# propulsion_shield.net
KiCad netlist of a schematic drawn in EAGLE
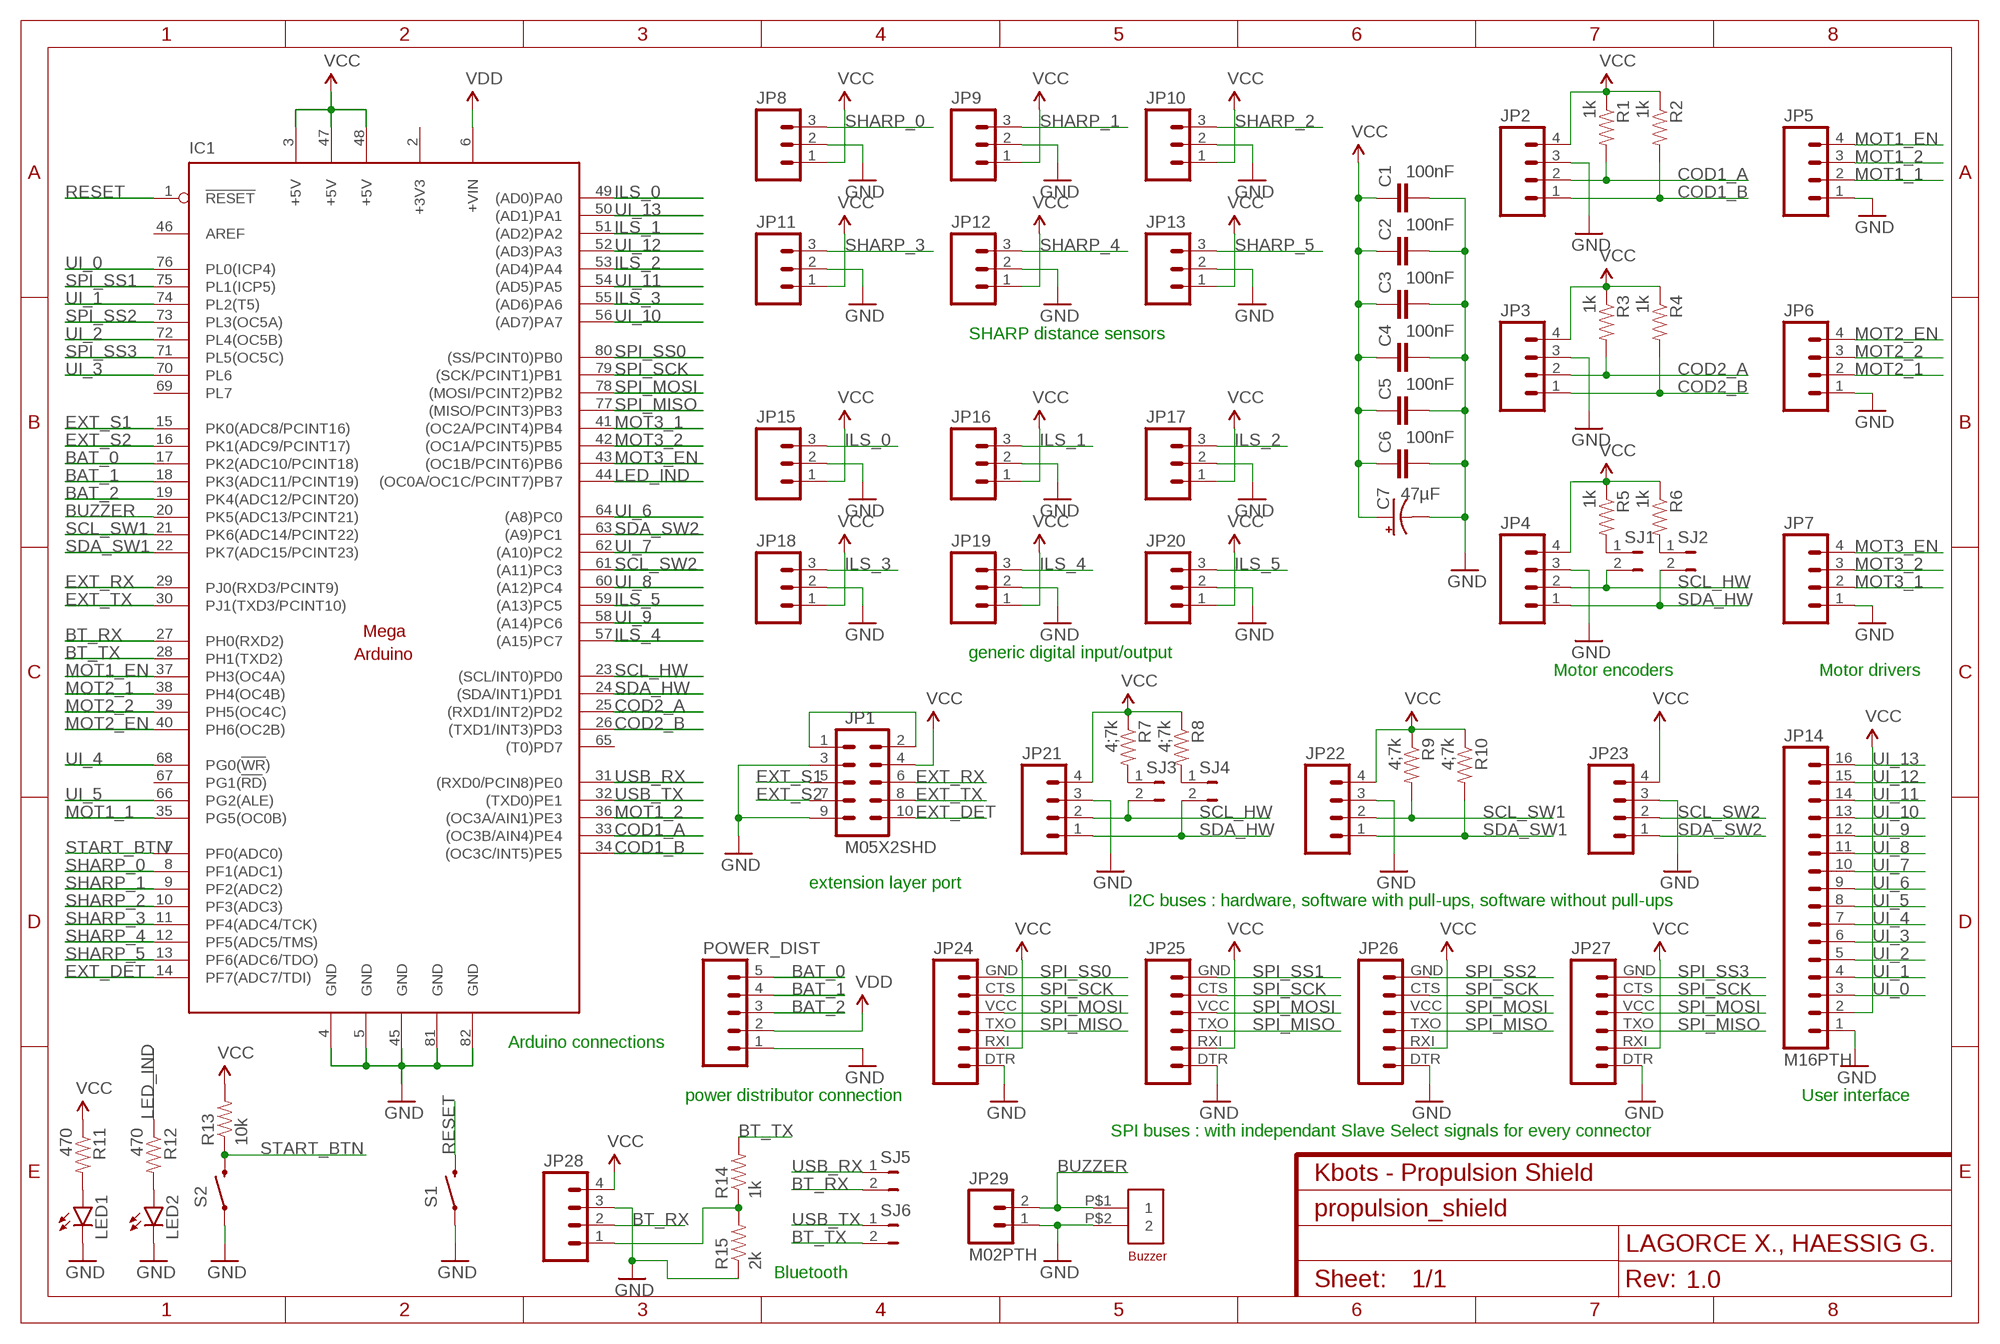
[diagram p0: schematic, sheet 1]

(export (version "E")
  (design (tool "Eeschema 10.0.6"))
  (components
    (comp (ref "C1")
      (value "100nF")
      (footprint "eagle-import:1206")
      (libsource (lib "eagle-import") (part "CAP1206"))
    )
    (comp (ref "C2")
      (value "100nF")
      (footprint "eagle-import:1206")
      (libsource (lib "eagle-import") (part "CAP1206"))
    )
    (comp (ref "C3")
      (value "100nF")
      (footprint "eagle-import:1206")
      (libsource (lib "eagle-import") (part "CAP1206"))
    )
    (comp (ref "C4")
      (value "100nF")
      (footprint "eagle-import:1206")
      (libsource (lib "eagle-import") (part "CAP1206"))
    )
    (comp (ref "C5")
      (value "100nF")
      (footprint "eagle-import:1206")
      (libsource (lib "eagle-import") (part "CAP1206"))
    )
    (comp (ref "C6")
      (value "100nF")
      (footprint "eagle-import:1206")
      (libsource (lib "eagle-import") (part "CAP1206"))
    )
    (comp (ref "C7")
      (value "47µF")
      (footprint "eagle-import:PANASONIC_D")
      (libsource (lib "eagle-import") (part "47UF-50V-20%(ELECT)"))
    )
    (comp (ref "IC1")
      (value "MEGAARDUINO_13")
      (footprint "eagle-import:MEGA_ARDUINO_NO_HOLE")
      (libsource (lib "eagle-import") (part "MEGAARDUINO_13"))
    )
    (comp (ref "JP1")
      (value "M05X2SHD")
      (footprint "eagle-import:2X5-SHROUDED")
      (libsource (lib "eagle-import") (part "M05X2SHD"))
    )
    (comp (ref "JP2")
      (value "M04PTH")
      (footprint "eagle-import:1X04")
      (libsource (lib "eagle-import") (part "M04PTH"))
    )
    (comp (ref "JP3")
      (value "M04PTH")
      (footprint "eagle-import:1X04")
      (libsource (lib "eagle-import") (part "M04PTH"))
    )
    (comp (ref "JP4")
      (value "M04PTH")
      (footprint "eagle-import:1X04")
      (libsource (lib "eagle-import") (part "M04PTH"))
    )
    (comp (ref "JP5")
      (value "M04PTH")
      (footprint "eagle-import:1X04")
      (libsource (lib "eagle-import") (part "M04PTH"))
    )
    (comp (ref "JP6")
      (value "M04PTH")
      (footprint "eagle-import:1X04")
      (libsource (lib "eagle-import") (part "M04PTH"))
    )
    (comp (ref "JP7")
      (value "M04PTH")
      (footprint "eagle-import:1X04")
      (libsource (lib "eagle-import") (part "M04PTH"))
    )
    (comp (ref "JP8")
      (value "M03PTH")
      (footprint "eagle-import:1X03")
      (libsource (lib "eagle-import") (part "M03PTH"))
    )
    (comp (ref "JP9")
      (value "M03PTH")
      (footprint "eagle-import:1X03")
      (libsource (lib "eagle-import") (part "M03PTH"))
    )
    (comp (ref "JP10")
      (value "M03PTH")
      (footprint "eagle-import:1X03")
      (libsource (lib "eagle-import") (part "M03PTH"))
    )
    (comp (ref "JP11")
      (value "M03PTH")
      (footprint "eagle-import:1X03")
      (libsource (lib "eagle-import") (part "M03PTH"))
    )
    (comp (ref "JP12")
      (value "M03PTH")
      (footprint "eagle-import:1X03")
      (libsource (lib "eagle-import") (part "M03PTH"))
    )
    (comp (ref "JP13")
      (value "M03PTH")
      (footprint "eagle-import:1X03")
      (libsource (lib "eagle-import") (part "M03PTH"))
    )
    (comp (ref "JP14")
      (value "M16PTH")
      (footprint "eagle-import:1X16")
      (libsource (lib "eagle-import") (part "M16PTH"))
    )
    (comp (ref "JP15")
      (value "M03PTH")
      (footprint "eagle-import:1X03")
      (libsource (lib "eagle-import") (part "M03PTH"))
    )
    (comp (ref "JP16")
      (value "M03PTH")
      (footprint "eagle-import:1X03")
      (libsource (lib "eagle-import") (part "M03PTH"))
    )
    (comp (ref "JP17")
      (value "M03PTH")
      (footprint "eagle-import:1X03")
      (libsource (lib "eagle-import") (part "M03PTH"))
    )
    (comp (ref "JP18")
      (value "M03PTH")
      (footprint "eagle-import:1X03")
      (libsource (lib "eagle-import") (part "M03PTH"))
    )
    (comp (ref "JP19")
      (value "M03PTH")
      (footprint "eagle-import:1X03")
      (libsource (lib "eagle-import") (part "M03PTH"))
    )
    (comp (ref "JP20")
      (value "M03PTH")
      (footprint "eagle-import:1X03")
      (libsource (lib "eagle-import") (part "M03PTH"))
    )
    (comp (ref "JP21")
      (value "M04PTH")
      (footprint "eagle-import:1X04")
      (libsource (lib "eagle-import") (part "M04PTH"))
    )
    (comp (ref "JP22")
      (value "M04PTH")
      (footprint "eagle-import:1X04")
      (libsource (lib "eagle-import") (part "M04PTH"))
    )
    (comp (ref "JP23")
      (value "M04PTH")
      (footprint "eagle-import:1X04")
      (libsource (lib "eagle-import") (part "M04PTH"))
    )
    (comp (ref "JP24")
      (value "M06SIP")
      (footprint "eagle-import:1X06")
      (libsource (lib "eagle-import") (part "M06SIP"))
    )
    (comp (ref "JP25")
      (value "M06SIP")
      (footprint "eagle-import:1X06")
      (libsource (lib "eagle-import") (part "M06SIP"))
    )
    (comp (ref "JP26")
      (value "M06SIP")
      (footprint "eagle-import:1X06")
      (libsource (lib "eagle-import") (part "M06SIP"))
    )
    (comp (ref "JP27")
      (value "M06SIP")
      (footprint "eagle-import:1X06")
      (libsource (lib "eagle-import") (part "M06SIP"))
    )
    (comp (ref "JP28")
      (value "M04PTH")
      (footprint "eagle-import:1X04")
      (libsource (lib "eagle-import") (part "M04PTH"))
    )
    (comp (ref "JP29")
      (value "M02PTH")
      (footprint "eagle-import:1X02")
      (libsource (lib "eagle-import") (part "M02PTH"))
    )
    (comp (ref "LED1")
      (value "LED1206")
      (footprint "eagle-import:LED-1206")
      (libsource (lib "eagle-import") (part "LED1206"))
    )
    (comp (ref "LED2")
      (value "LED1206")
      (footprint "eagle-import:LED-1206")
      (libsource (lib "eagle-import") (part "LED1206"))
    )
    (comp (ref "POWER_DIST")
      (value "M05PTH")
      (footprint "eagle-import:1X05")
      (libsource (lib "eagle-import") (part "M05PTH"))
    )
    (comp (ref "R1")
      (value "1k")
      (footprint "eagle-import:1206")
      (libsource (lib "eagle-import") (part "RESISTOR1206"))
    )
    (comp (ref "R2")
      (value "1k")
      (footprint "eagle-import:1206")
      (libsource (lib "eagle-import") (part "RESISTOR1206"))
    )
    (comp (ref "R3")
      (value "1k")
      (footprint "eagle-import:1206")
      (libsource (lib "eagle-import") (part "RESISTOR1206"))
    )
    (comp (ref "R4")
      (value "1k")
      (footprint "eagle-import:1206")
      (libsource (lib "eagle-import") (part "RESISTOR1206"))
    )
    (comp (ref "R5")
      (value "1k")
      (footprint "eagle-import:1206")
      (libsource (lib "eagle-import") (part "RESISTOR1206"))
    )
    (comp (ref "R6")
      (value "1k")
      (footprint "eagle-import:1206")
      (libsource (lib "eagle-import") (part "RESISTOR1206"))
    )
    (comp (ref "R7")
      (value "4;7k")
      (footprint "eagle-import:1206")
      (libsource (lib "eagle-import") (part "RESISTOR1206"))
    )
    (comp (ref "R8")
      (value "4;7k")
      (footprint "eagle-import:1206")
      (libsource (lib "eagle-import") (part "RESISTOR1206"))
    )
    (comp (ref "R9")
      (value "4;7k")
      (footprint "eagle-import:1206")
      (libsource (lib "eagle-import") (part "RESISTOR1206"))
    )
    (comp (ref "R10")
      (value "4;7k")
      (footprint "eagle-import:1206")
      (libsource (lib "eagle-import") (part "RESISTOR1206"))
    )
    (comp (ref "R11")
      (value "470")
      (footprint "eagle-import:1206")
      (libsource (lib "eagle-import") (part "RESISTOR1206"))
    )
    (comp (ref "R12")
      (value "470")
      (footprint "eagle-import:1206")
      (libsource (lib "eagle-import") (part "RESISTOR1206"))
    )
    (comp (ref "R13")
      (value "10k")
      (footprint "eagle-import:1206")
      (libsource (lib "eagle-import") (part "RESISTOR1206"))
    )
    (comp (ref "R14")
      (value "1k")
      (footprint "eagle-import:1206")
      (libsource (lib "eagle-import") (part "RESISTOR1206"))
    )
    (comp (ref "R15")
      (value "2k")
      (footprint "eagle-import:1206")
      (libsource (lib "eagle-import") (part "RESISTOR1206"))
    )
    (comp (ref "S1")
      (value "SWITCH-MOMENTARY-2PTH")
      (footprint "eagle-import:TACTILE-PTH")
      (libsource (lib "eagle-import") (part "SWITCH-MOMENTARY-2PTH"))
    )
    (comp (ref "S2")
      (value "SWITCH-MOMENTARY-2PTH")
      (footprint "eagle-import:TACTILE-PTH")
      (libsource (lib "eagle-import") (part "SWITCH-MOMENTARY-2PTH"))
    )
    (comp (ref "SJ1")
      (value "JUMPER-PTH-2-NO")
      (footprint "eagle-import:PTH-JUMPER-2-NO_NO_SILK")
      (libsource (lib "eagle-import") (part "JUMPER-PTH-2-NO"))
    )
    (comp (ref "SJ2")
      (value "JUMPER-PTH-2-NO")
      (footprint "eagle-import:PTH-JUMPER-2-NO_NO_SILK")
      (libsource (lib "eagle-import") (part "JUMPER-PTH-2-NO"))
    )
    (comp (ref "SJ3")
      (value "JUMPER-PTH-2-NO")
      (footprint "eagle-import:PTH-JUMPER-2-NO_NO_SILK")
      (libsource (lib "eagle-import") (part "JUMPER-PTH-2-NO"))
    )
    (comp (ref "SJ4")
      (value "JUMPER-PTH-2-NO")
      (footprint "eagle-import:PTH-JUMPER-2-NO_NO_SILK")
      (libsource (lib "eagle-import") (part "JUMPER-PTH-2-NO"))
    )
    (comp (ref "SJ5")
      (value "JUMPER-PTH-2-NO")
      (footprint "eagle-import:PTH-JUMPER-2-NO_NO_SILK")
      (libsource (lib "eagle-import") (part "JUMPER-PTH-2-NO"))
    )
    (comp (ref "SJ6")
      (value "JUMPER-PTH-2-NO")
      (footprint "eagle-import:PTH-JUMPER-2-NO_NO_SILK")
      (libsource (lib "eagle-import") (part "JUMPER-PTH-2-NO"))
    )
    (comp (ref "U$1")
      (value "BUZZER")
      (footprint "eagle-import:BUZZER")
      (libsource (lib "eagle-import") (part "BUZZER"))
    )
  )
  (nets
    (net (code "1") (name "/+3V3") (class "Default")
      (node (ref "IC1") (pin "2") (pinfunction "+3V3_2") (pintype "power_in"))
    )
    (net (code "2") (name "/BAT_0") (class "Default")
      (node (ref "IC1") (pin "17") (pinfunction "PK2(ADC10/PCINT18)_17") (pintype "bidirectional"))
      (node (ref "POWER_DIST") (pin "5") (pinfunction "5_5") (pintype "passive"))
    )
    (net (code "3") (name "/BAT_1") (class "Default")
      (node (ref "IC1") (pin "18") (pinfunction "PK3(ADC11/PCINT19)_18") (pintype "bidirectional"))
      (node (ref "POWER_DIST") (pin "4") (pinfunction "4_4") (pintype "passive"))
    )
    (net (code "4") (name "/BAT_2") (class "Default")
      (node (ref "IC1") (pin "19") (pinfunction "PK4(ADC12/PCINT20)_19") (pintype "bidirectional"))
      (node (ref "POWER_DIST") (pin "3") (pinfunction "3_3") (pintype "passive"))
    )
    (net (code "5") (name "/BT_RX") (class "Default")
      (node (ref "IC1") (pin "27") (pinfunction "PH0(RXD2)_27") (pintype "bidirectional"))
      (node (ref "JP28") (pin "2") (pinfunction "2_2") (pintype "passive"))
      (node (ref "SJ5") (pin "2") (pinfunction "2_2") (pintype "passive"))
    )
    (net (code "6") (name "/BT_TX") (class "Default")
      (node (ref "IC1") (pin "28") (pinfunction "PH1(TXD2)_28") (pintype "bidirectional"))
      (node (ref "R14") (pin "2") (pinfunction "2_2") (pintype "passive"))
      (node (ref "SJ6") (pin "2") (pinfunction "2_2") (pintype "passive"))
    )
    (net (code "7") (name "/BUZZER") (class "Default")
      (node (ref "IC1") (pin "20") (pinfunction "PK5(ADC13/PCINT21)_20") (pintype "bidirectional"))
      (node (ref "JP29") (pin "2") (pinfunction "2_2") (pintype "passive"))
      (node (ref "U$1") (pin "P$1") (pinfunction "1_P$1") (pintype "bidirectional"))
    )
    (net (code "8") (name "/COD1_A") (class "Default")
      (node (ref "IC1") (pin "33") (pinfunction "(OC3B/AIN4)PE4_33") (pintype "bidirectional"))
      (node (ref "JP2") (pin "2") (pinfunction "2_2") (pintype "passive"))
      (node (ref "R1") (pin "2") (pinfunction "2_2") (pintype "passive"))
    )
    (net (code "9") (name "/COD1_B") (class "Default")
      (node (ref "IC1") (pin "34") (pinfunction "(OC3C/INT5)PE5_34") (pintype "bidirectional"))
      (node (ref "JP2") (pin "1") (pinfunction "1_1") (pintype "passive"))
      (node (ref "R2") (pin "2") (pinfunction "2_2") (pintype "passive"))
    )
    (net (code "10") (name "/COD2_A") (class "Default")
      (node (ref "IC1") (pin "25") (pinfunction "(RXD1/INT2)PD2_25") (pintype "bidirectional"))
      (node (ref "JP3") (pin "2") (pinfunction "2_2") (pintype "passive"))
      (node (ref "R3") (pin "2") (pinfunction "2_2") (pintype "passive"))
    )
    (net (code "11") (name "/COD2_B") (class "Default")
      (node (ref "IC1") (pin "26") (pinfunction "(TXD1/INT3)PD3_26") (pintype "bidirectional"))
      (node (ref "JP3") (pin "1") (pinfunction "1_1") (pintype "passive"))
      (node (ref "R4") (pin "2") (pinfunction "2_2") (pintype "passive"))
    )
    (net (code "12") (name "/EXT_DET") (class "Default")
      (node (ref "IC1") (pin "14") (pinfunction "PF7(ADC7/TDI)_14") (pintype "bidirectional"))
      (node (ref "JP1") (pin "10") (pinfunction "10_10") (pintype "passive"))
    )
    (net (code "13") (name "/EXT_RX") (class "Default")
      (node (ref "IC1") (pin "29") (pinfunction "PJ0(RXD3/PCINT9)_29") (pintype "bidirectional"))
      (node (ref "JP1") (pin "6") (pinfunction "6_6") (pintype "passive"))
    )
    (net (code "14") (name "/EXT_S1") (class "Default")
      (node (ref "IC1") (pin "15") (pinfunction "PK0(ADC8/PCINT16)_15") (pintype "bidirectional"))
      (node (ref "JP1") (pin "5") (pinfunction "5_5") (pintype "passive"))
    )
    (net (code "15") (name "/EXT_S2") (class "Default")
      (node (ref "IC1") (pin "16") (pinfunction "PK1(ADC9/PCINT17)_16") (pintype "bidirectional"))
      (node (ref "JP1") (pin "7") (pinfunction "7_7") (pintype "passive"))
    )
    (net (code "16") (name "/EXT_TX") (class "Default")
      (node (ref "IC1") (pin "30") (pinfunction "PJ1(TXD3/PCINT10)_30") (pintype "bidirectional"))
      (node (ref "JP1") (pin "8") (pinfunction "8_8") (pintype "passive"))
    )
    (net (code "17") (name "/ILS_0") (class "Default")
      (node (ref "IC1") (pin "49") (pinfunction "(AD0)PA0_49") (pintype "bidirectional"))
      (node (ref "JP15") (pin "3") (pinfunction "3_3") (pintype "passive"))
    )
    (net (code "18") (name "/ILS_1") (class "Default")
      (node (ref "IC1") (pin "51") (pinfunction "(AD2)PA2_51") (pintype "bidirectional"))
      (node (ref "JP16") (pin "3") (pinfunction "3_3") (pintype "passive"))
    )
    (net (code "19") (name "/ILS_2") (class "Default")
      (node (ref "IC1") (pin "53") (pinfunction "(AD4)PA4_53") (pintype "bidirectional"))
      (node (ref "JP17") (pin "3") (pinfunction "3_3") (pintype "passive"))
    )
    (net (code "20") (name "/ILS_3") (class "Default")
      (node (ref "IC1") (pin "55") (pinfunction "(AD6)PA6_55") (pintype "bidirectional"))
      (node (ref "JP18") (pin "3") (pinfunction "3_3") (pintype "passive"))
    )
    (net (code "21") (name "/ILS_4") (class "Default")
      (node (ref "IC1") (pin "57") (pinfunction "(A15)PC7_57") (pintype "bidirectional"))
      (node (ref "JP19") (pin "3") (pinfunction "3_3") (pintype "passive"))
    )
    (net (code "22") (name "/ILS_5") (class "Default")
      (node (ref "IC1") (pin "59") (pinfunction "(A13)PC5_59") (pintype "bidirectional"))
      (node (ref "JP20") (pin "3") (pinfunction "3_3") (pintype "passive"))
    )
    (net (code "23") (name "/LED_IND") (class "Default")
      (node (ref "IC1") (pin "44") (pinfunction "(OC0A/OC1C/PCINT7)PB7_44") (pintype "bidirectional"))
      (node (ref "R12") (pin "1") (pinfunction "1_1") (pintype "passive"))
    )
    (net (code "24") (name "/MOT1_1") (class "Default")
      (node (ref "IC1") (pin "35") (pinfunction "PG5(OC0B)_35") (pintype "bidirectional"))
      (node (ref "JP5") (pin "2") (pinfunction "2_2") (pintype "passive"))
    )
    (net (code "25") (name "/MOT1_2") (class "Default")
      (node (ref "IC1") (pin "36") (pinfunction "(OC3A/AIN1)PE3_36") (pintype "bidirectional"))
      (node (ref "JP5") (pin "3") (pinfunction "3_3") (pintype "passive"))
    )
    (net (code "26") (name "/MOT1_EN") (class "Default")
      (node (ref "IC1") (pin "37") (pinfunction "PH3(OC4A)_37") (pintype "bidirectional"))
      (node (ref "JP5") (pin "4") (pinfunction "4_4") (pintype "passive"))
    )
    (net (code "27") (name "/MOT2_1") (class "Default")
      (node (ref "IC1") (pin "38") (pinfunction "PH4(OC4B)_38") (pintype "bidirectional"))
      (node (ref "JP6") (pin "2") (pinfunction "2_2") (pintype "passive"))
    )
    (net (code "28") (name "/MOT2_2") (class "Default")
      (node (ref "IC1") (pin "39") (pinfunction "PH5(OC4C)_39") (pintype "bidirectional"))
      (node (ref "JP6") (pin "3") (pinfunction "3_3") (pintype "passive"))
    )
    (net (code "29") (name "/MOT2_EN") (class "Default")
      (node (ref "IC1") (pin "40") (pinfunction "PH6(OC2B)_40") (pintype "bidirectional"))
      (node (ref "JP6") (pin "4") (pinfunction "4_4") (pintype "passive"))
    )
    (net (code "30") (name "/MOT3_1") (class "Default")
      (node (ref "IC1") (pin "41") (pinfunction "(OC2A/PCINT4)PB4_41") (pintype "bidirectional"))
      (node (ref "JP7") (pin "2") (pinfunction "2_2") (pintype "passive"))
    )
    (net (code "31") (name "/MOT3_2") (class "Default")
      (node (ref "IC1") (pin "42") (pinfunction "(OC1A/PCINT5)PB5_42") (pintype "bidirectional"))
      (node (ref "JP7") (pin "3") (pinfunction "3_3") (pintype "passive"))
    )
    (net (code "32") (name "/MOT3_EN") (class "Default")
      (node (ref "IC1") (pin "43") (pinfunction "(OC1B/PCINT6)PB6_43") (pintype "bidirectional"))
      (node (ref "JP7") (pin "4") (pinfunction "4_4") (pintype "passive"))
    )
    (net (code "33") (name "/RESET") (class "Default")
      (node (ref "IC1") (pin "1") (pinfunction "~{RESET}_1") (pintype "bidirectional"))
      (node (ref "S1") (pin "3") (pinfunction "2_3") (pintype "passive"))
    )
    (net (code "34") (name "/SCL_HW") (class "Default")
      (node (ref "IC1") (pin "23") (pinfunction "(SCL/INT0)PD0_23") (pintype "bidirectional"))
      (node (ref "JP21") (pin "2") (pinfunction "2_2") (pintype "passive"))
      (node (ref "JP4") (pin "2") (pinfunction "2_2") (pintype "passive"))
      (node (ref "SJ1") (pin "2") (pinfunction "2_2") (pintype "passive"))
      (node (ref "SJ3") (pin "2") (pinfunction "2_2") (pintype "passive"))
    )
    (net (code "35") (name "/SCL_SW1") (class "Default")
      (node (ref "IC1") (pin "21") (pinfunction "PK6(ADC14/PCINT22)_21") (pintype "bidirectional"))
      (node (ref "JP22") (pin "2") (pinfunction "2_2") (pintype "passive"))
      (node (ref "R9") (pin "2") (pinfunction "2_2") (pintype "passive"))
    )
    (net (code "36") (name "/SCL_SW2") (class "Default")
      (node (ref "IC1") (pin "61") (pinfunction "(A11)PC3_61") (pintype "bidirectional"))
      (node (ref "JP23") (pin "2") (pinfunction "2_2") (pintype "passive"))
    )
    (net (code "37") (name "/SDA_HW") (class "Default")
      (node (ref "IC1") (pin "24") (pinfunction "(SDA/INT1)PD1_24") (pintype "bidirectional"))
      (node (ref "JP21") (pin "1") (pinfunction "1_1") (pintype "passive"))
      (node (ref "JP4") (pin "1") (pinfunction "1_1") (pintype "passive"))
      (node (ref "SJ2") (pin "2") (pinfunction "2_2") (pintype "passive"))
      (node (ref "SJ4") (pin "2") (pinfunction "2_2") (pintype "passive"))
    )
    (net (code "38") (name "/SDA_SW1") (class "Default")
      (node (ref "IC1") (pin "22") (pinfunction "PK7(ADC15/PCINT23)_22") (pintype "bidirectional"))
      (node (ref "JP22") (pin "1") (pinfunction "1_1") (pintype "passive"))
      (node (ref "R10") (pin "2") (pinfunction "2_2") (pintype "passive"))
    )
    (net (code "39") (name "/SDA_SW2") (class "Default")
      (node (ref "IC1") (pin "63") (pinfunction "(A9)PC1_63") (pintype "bidirectional"))
      (node (ref "JP23") (pin "1") (pinfunction "1_1") (pintype "passive"))
    )
    (net (code "40") (name "/SHARP_0") (class "Default")
      (node (ref "IC1") (pin "8") (pinfunction "PF1(ADC1)_8") (pintype "bidirectional"))
      (node (ref "JP8") (pin "3") (pinfunction "3_3") (pintype "passive"))
    )
    (net (code "41") (name "/SHARP_1") (class "Default")
      (node (ref "IC1") (pin "9") (pinfunction "PF2(ADC2)_9") (pintype "bidirectional"))
      (node (ref "JP9") (pin "3") (pinfunction "3_3") (pintype "passive"))
    )
    (net (code "42") (name "/SHARP_2") (class "Default")
      (node (ref "IC1") (pin "10") (pinfunction "PF3(ADC3)_10") (pintype "bidirectional"))
      (node (ref "JP10") (pin "3") (pinfunction "3_3") (pintype "passive"))
    )
    (net (code "43") (name "/SHARP_3") (class "Default")
      (node (ref "IC1") (pin "11") (pinfunction "PF4(ADC4/TCK)_11") (pintype "bidirectional"))
      (node (ref "JP11") (pin "3") (pinfunction "3_3") (pintype "passive"))
    )
    (net (code "44") (name "/SHARP_4") (class "Default")
      (node (ref "IC1") (pin "12") (pinfunction "PF5(ADC5/TMS)_12") (pintype "bidirectional"))
      (node (ref "JP12") (pin "3") (pinfunction "3_3") (pintype "passive"))
    )
    (net (code "45") (name "/SHARP_5") (class "Default")
      (node (ref "IC1") (pin "13") (pinfunction "PF6(ADC6/TDO)_13") (pintype "bidirectional"))
      (node (ref "JP13") (pin "3") (pinfunction "3_3") (pintype "passive"))
    )
    (net (code "46") (name "/SPI_MISO") (class "Default")
      (node (ref "IC1") (pin "77") (pinfunction "(MISO/PCINT3)PB3_77") (pintype "bidirectional"))
      (node (ref "JP24") (pin "TXO") (pinfunction "3_TXO") (pintype "passive"))
      (node (ref "JP25") (pin "TXO") (pinfunction "3_TXO") (pintype "passive"))
      (node (ref "JP26") (pin "TXO") (pinfunction "3_TXO") (pintype "passive"))
      (node (ref "JP27") (pin "TXO") (pinfunction "3_TXO") (pintype "passive"))
    )
    (net (code "47") (name "/SPI_MOSI") (class "Default")
      (node (ref "IC1") (pin "78") (pinfunction "(MOSI/PCINT2)PB2_78") (pintype "bidirectional"))
      (node (ref "JP24") (pin "VCC") (pinfunction "4_VCC") (pintype "passive"))
      (node (ref "JP25") (pin "VCC") (pinfunction "4_VCC") (pintype "passive"))
      (node (ref "JP26") (pin "VCC") (pinfunction "4_VCC") (pintype "passive"))
      (node (ref "JP27") (pin "VCC") (pinfunction "4_VCC") (pintype "passive"))
    )
    (net (code "48") (name "/SPI_SCK") (class "Default")
      (node (ref "IC1") (pin "79") (pinfunction "(SCK/PCINT1)PB1_79") (pintype "bidirectional"))
      (node (ref "JP24") (pin "CTS") (pinfunction "5_CTS") (pintype "passive"))
      (node (ref "JP25") (pin "CTS") (pinfunction "5_CTS") (pintype "passive"))
      (node (ref "JP26") (pin "CTS") (pinfunction "5_CTS") (pintype "passive"))
      (node (ref "JP27") (pin "CTS") (pinfunction "5_CTS") (pintype "passive"))
    )
    (net (code "49") (name "/SPI_SS0") (class "Default")
      (node (ref "IC1") (pin "80") (pinfunction "(SS/PCINT0)PB0_80") (pintype "bidirectional"))
      (node (ref "JP24") (pin "GND") (pinfunction "6_GND") (pintype "passive"))
    )
    (net (code "50") (name "/SPI_SS1") (class "Default")
      (node (ref "IC1") (pin "75") (pinfunction "PL1(ICP5)_75") (pintype "bidirectional"))
      (node (ref "JP25") (pin "GND") (pinfunction "6_GND") (pintype "passive"))
    )
    (net (code "51") (name "/SPI_SS2") (class "Default")
      (node (ref "IC1") (pin "73") (pinfunction "PL3(OC5A)_73") (pintype "bidirectional"))
      (node (ref "JP26") (pin "GND") (pinfunction "6_GND") (pintype "passive"))
    )
    (net (code "52") (name "/SPI_SS3") (class "Default")
      (node (ref "IC1") (pin "71") (pinfunction "PL5(OC5C)_71") (pintype "bidirectional"))
      (node (ref "JP27") (pin "GND") (pinfunction "6_GND") (pintype "passive"))
    )
    (net (code "53") (name "/START_BTN") (class "Default")
      (node (ref "IC1") (pin "7") (pinfunction "PF0(ADC0)_7") (pintype "bidirectional"))
      (node (ref "R13") (pin "1") (pinfunction "1_1") (pintype "passive"))
      (node (ref "S2") (pin "3") (pinfunction "2_3") (pintype "passive"))
    )
    (net (code "54") (name "/UI_0") (class "Default")
      (node (ref "IC1") (pin "76") (pinfunction "PL0(ICP4)_76") (pintype "bidirectional"))
      (node (ref "JP14") (pin "3") (pinfunction "3_3") (pintype "passive"))
    )
    (net (code "55") (name "/UI_1") (class "Default")
      (node (ref "IC1") (pin "74") (pinfunction "PL2(T5)_74") (pintype "bidirectional"))
      (node (ref "JP14") (pin "4") (pinfunction "4_4") (pintype "passive"))
    )
    (net (code "56") (name "/UI_2") (class "Default")
      (node (ref "IC1") (pin "72") (pinfunction "PL4(OC5B)_72") (pintype "bidirectional"))
      (node (ref "JP14") (pin "5") (pinfunction "5_5") (pintype "passive"))
    )
    (net (code "57") (name "/UI_3") (class "Default")
      (node (ref "IC1") (pin "70") (pinfunction "PL6_70") (pintype "bidirectional"))
      (node (ref "JP14") (pin "6") (pinfunction "6_6") (pintype "passive"))
    )
    (net (code "58") (name "/UI_4") (class "Default")
      (node (ref "IC1") (pin "68") (pinfunction "PG0(~{WR})_68") (pintype "bidirectional"))
      (node (ref "JP14") (pin "7") (pinfunction "7_7") (pintype "passive"))
    )
    (net (code "59") (name "/UI_5") (class "Default")
      (node (ref "IC1") (pin "66") (pinfunction "PG2(ALE)_66") (pintype "bidirectional"))
      (node (ref "JP14") (pin "8") (pinfunction "8_8") (pintype "passive"))
    )
    (net (code "60") (name "/UI_6") (class "Default")
      (node (ref "IC1") (pin "64") (pinfunction "(A8)PC0_64") (pintype "bidirectional"))
      (node (ref "JP14") (pin "9") (pinfunction "9_9") (pintype "passive"))
    )
    (net (code "61") (name "/UI_7") (class "Default")
      (node (ref "IC1") (pin "62") (pinfunction "(A10)PC2_62") (pintype "bidirectional"))
      (node (ref "JP14") (pin "10") (pinfunction "10_10") (pintype "passive"))
    )
    (net (code "62") (name "/UI_8") (class "Default")
      (node (ref "IC1") (pin "60") (pinfunction "(A12)PC4_60") (pintype "bidirectional"))
      (node (ref "JP14") (pin "11") (pinfunction "11_11") (pintype "passive"))
    )
    (net (code "63") (name "/UI_9") (class "Default")
      (node (ref "IC1") (pin "58") (pinfunction "(A14)PC6_58") (pintype "bidirectional"))
      (node (ref "JP14") (pin "12") (pinfunction "12_12") (pintype "passive"))
    )
    (net (code "64") (name "/UI_10") (class "Default")
      (node (ref "IC1") (pin "56") (pinfunction "(AD7)PA7_56") (pintype "bidirectional"))
      (node (ref "JP14") (pin "13") (pinfunction "13_13") (pintype "passive"))
    )
    (net (code "65") (name "/UI_11") (class "Default")
      (node (ref "IC1") (pin "54") (pinfunction "(AD5)PA5_54") (pintype "bidirectional"))
      (node (ref "JP14") (pin "14") (pinfunction "14_14") (pintype "passive"))
    )
    (net (code "66") (name "/UI_12") (class "Default")
      (node (ref "IC1") (pin "52") (pinfunction "(AD3)PA3_52") (pintype "bidirectional"))
      (node (ref "JP14") (pin "15") (pinfunction "15_15") (pintype "passive"))
    )
    (net (code "67") (name "/UI_13") (class "Default")
      (node (ref "IC1") (pin "50") (pinfunction "(AD1)PA1_50") (pintype "bidirectional"))
      (node (ref "JP14") (pin "16") (pinfunction "16_16") (pintype "passive"))
    )
    (net (code "68") (name "/USB_RX") (class "Default")
      (node (ref "IC1") (pin "31") (pinfunction "(RXD0/PCIN8)PE0_31") (pintype "bidirectional"))
      (node (ref "SJ5") (pin "1") (pinfunction "1_1") (pintype "passive"))
    )
    (net (code "69") (name "/USB_TX") (class "Default")
      (node (ref "IC1") (pin "32") (pinfunction "(TXD0)PE1_32") (pintype "bidirectional"))
      (node (ref "SJ6") (pin "1") (pinfunction "1_1") (pintype "passive"))
    )
    (net (code "70") (name "GND") (class "Default")
      (node (ref "C1") (pin "2") (pinfunction "2_2") (pintype "passive"))
      (node (ref "C2") (pin "2") (pinfunction "2_2") (pintype "passive"))
      (node (ref "C3") (pin "2") (pinfunction "2_2") (pintype "passive"))
      (node (ref "C4") (pin "2") (pinfunction "2_2") (pintype "passive"))
      (node (ref "C5") (pin "2") (pinfunction "2_2") (pintype "passive"))
      (node (ref "C6") (pin "2") (pinfunction "2_2") (pintype "passive"))
      (node (ref "C7") (pin "-") (pinfunction "-_-") (pintype "passive"))
      (node (ref "IC1") (pin "4") (pinfunction "GND_4") (pintype "power_in"))
      (node (ref "IC1") (pin "45") (pinfunction "GND_45") (pintype "power_in"))
      (node (ref "IC1") (pin "5") (pinfunction "GND_5") (pintype "power_in"))
      (node (ref "IC1") (pin "81") (pinfunction "GND_81") (pintype "power_in"))
      (node (ref "IC1") (pin "82") (pinfunction "GND_82") (pintype "power_in"))
      (node (ref "JP1") (pin "3") (pinfunction "3_3") (pintype "passive"))
      (node (ref "JP1") (pin "9") (pinfunction "9_9") (pintype "passive"))
      (node (ref "JP10") (pin "2") (pinfunction "2_2") (pintype "passive"))
      (node (ref "JP11") (pin "2") (pinfunction "2_2") (pintype "passive"))
      (node (ref "JP12") (pin "2") (pinfunction "2_2") (pintype "passive"))
      (node (ref "JP13") (pin "2") (pinfunction "2_2") (pintype "passive"))
      (node (ref "JP14") (pin "1") (pinfunction "1_1") (pintype "passive"))
      (node (ref "JP15") (pin "2") (pinfunction "2_2") (pintype "passive"))
      (node (ref "JP16") (pin "2") (pinfunction "2_2") (pintype "passive"))
      (node (ref "JP17") (pin "2") (pinfunction "2_2") (pintype "passive"))
      (node (ref "JP18") (pin "2") (pinfunction "2_2") (pintype "passive"))
      (node (ref "JP19") (pin "2") (pinfunction "2_2") (pintype "passive"))
      (node (ref "JP2") (pin "3") (pinfunction "3_3") (pintype "passive"))
      (node (ref "JP20") (pin "2") (pinfunction "2_2") (pintype "passive"))
      (node (ref "JP21") (pin "3") (pinfunction "3_3") (pintype "passive"))
      (node (ref "JP22") (pin "3") (pinfunction "3_3") (pintype "passive"))
      (node (ref "JP23") (pin "3") (pinfunction "3_3") (pintype "passive"))
      (node (ref "JP24") (pin "DTR") (pinfunction "1_DTR") (pintype "passive"))
      (node (ref "JP25") (pin "DTR") (pinfunction "1_DTR") (pintype "passive"))
      (node (ref "JP26") (pin "DTR") (pinfunction "1_DTR") (pintype "passive"))
      (node (ref "JP27") (pin "DTR") (pinfunction "1_DTR") (pintype "passive"))
      (node (ref "JP28") (pin "3") (pinfunction "3_3") (pintype "passive"))
      (node (ref "JP29") (pin "1") (pinfunction "1_1") (pintype "passive"))
      (node (ref "JP3") (pin "3") (pinfunction "3_3") (pintype "passive"))
      (node (ref "JP4") (pin "3") (pinfunction "3_3") (pintype "passive"))
      (node (ref "JP5") (pin "1") (pinfunction "1_1") (pintype "passive"))
      (node (ref "JP6") (pin "1") (pinfunction "1_1") (pintype "passive"))
      (node (ref "JP7") (pin "1") (pinfunction "1_1") (pintype "passive"))
      (node (ref "JP8") (pin "2") (pinfunction "2_2") (pintype "passive"))
      (node (ref "JP9") (pin "2") (pinfunction "2_2") (pintype "passive"))
      (node (ref "LED1") (pin "C") (pinfunction "C_C") (pintype "passive"))
      (node (ref "LED2") (pin "C") (pinfunction "C_C") (pintype "passive"))
      (node (ref "POWER_DIST") (pin "1") (pinfunction "1_1") (pintype "passive"))
      (node (ref "R15") (pin "1") (pinfunction "1_1") (pintype "passive"))
      (node (ref "S1") (pin "1") (pinfunction "1_1") (pintype "passive"))
      (node (ref "S2") (pin "1") (pinfunction "1_1") (pintype "passive"))
      (node (ref "U$1") (pin "P$2") (pinfunction "2_P$2") (pintype "bidirectional"))
    )
    (net (code "71") (name "Net-(JP1-Pad1)") (class "Default")
      (node (ref "JP1") (pin "1") (pinfunction "1_1") (pintype "passive"))
      (node (ref "JP1") (pin "2") (pinfunction "2_2") (pintype "passive"))
    )
    (net (code "72") (name "Net-(JP28-Pad1)") (class "Default")
      (node (ref "JP28") (pin "1") (pinfunction "1_1") (pintype "passive"))
      (node (ref "R14") (pin "1") (pinfunction "1_1") (pintype "passive"))
      (node (ref "R15") (pin "2") (pinfunction "2_2") (pintype "passive"))
    )
    (net (code "73") (name "Net-(LED1-PadA)") (class "Default")
      (node (ref "LED1") (pin "A") (pinfunction "A_A") (pintype "passive"))
      (node (ref "R11") (pin "2") (pinfunction "2_2") (pintype "passive"))
    )
    (net (code "74") (name "Net-(LED2-PadA)") (class "Default")
      (node (ref "LED2") (pin "A") (pinfunction "A_A") (pintype "passive"))
      (node (ref "R12") (pin "2") (pinfunction "2_2") (pintype "passive"))
    )
    (net (code "75") (name "Net-(R5-Pad2)") (class "Default")
      (node (ref "R5") (pin "2") (pinfunction "2_2") (pintype "passive"))
      (node (ref "SJ1") (pin "1") (pinfunction "1_1") (pintype "passive"))
    )
    (net (code "76") (name "Net-(R6-Pad2)") (class "Default")
      (node (ref "R6") (pin "2") (pinfunction "2_2") (pintype "passive"))
      (node (ref "SJ2") (pin "1") (pinfunction "1_1") (pintype "passive"))
    )
    (net (code "77") (name "Net-(R7-Pad2)") (class "Default")
      (node (ref "R7") (pin "2") (pinfunction "2_2") (pintype "passive"))
      (node (ref "SJ3") (pin "1") (pinfunction "1_1") (pintype "passive"))
    )
    (net (code "78") (name "Net-(R8-Pad2)") (class "Default")
      (node (ref "R8") (pin "2") (pinfunction "2_2") (pintype "passive"))
      (node (ref "SJ4") (pin "1") (pinfunction "1_1") (pintype "passive"))
    )
    (net (code "79") (name "VCC") (class "Default")
      (node (ref "C1") (pin "1") (pinfunction "1_1") (pintype "passive"))
      (node (ref "C2") (pin "1") (pinfunction "1_1") (pintype "passive"))
      (node (ref "C3") (pin "1") (pinfunction "1_1") (pintype "passive"))
      (node (ref "C4") (pin "1") (pinfunction "1_1") (pintype "passive"))
      (node (ref "C5") (pin "1") (pinfunction "1_1") (pintype "passive"))
      (node (ref "C6") (pin "1") (pinfunction "1_1") (pintype "passive"))
      (node (ref "C7") (pin "+") (pinfunction "+_+") (pintype "passive"))
      (node (ref "IC1") (pin "3") (pinfunction "+5V_3") (pintype "power_in"))
      (node (ref "IC1") (pin "47") (pinfunction "+5V_47") (pintype "power_in"))
      (node (ref "IC1") (pin "48") (pinfunction "+5V_48") (pintype "power_in"))
      (node (ref "JP1") (pin "4") (pinfunction "4_4") (pintype "passive"))
      (node (ref "JP10") (pin "1") (pinfunction "1_1") (pintype "passive"))
      (node (ref "JP11") (pin "1") (pinfunction "1_1") (pintype "passive"))
      (node (ref "JP12") (pin "1") (pinfunction "1_1") (pintype "passive"))
      (node (ref "JP13") (pin "1") (pinfunction "1_1") (pintype "passive"))
      (node (ref "JP14") (pin "2") (pinfunction "2_2") (pintype "passive"))
      (node (ref "JP15") (pin "1") (pinfunction "1_1") (pintype "passive"))
      (node (ref "JP16") (pin "1") (pinfunction "1_1") (pintype "passive"))
      (node (ref "JP17") (pin "1") (pinfunction "1_1") (pintype "passive"))
      (node (ref "JP18") (pin "1") (pinfunction "1_1") (pintype "passive"))
      (node (ref "JP19") (pin "1") (pinfunction "1_1") (pintype "passive"))
      (node (ref "JP2") (pin "4") (pinfunction "4_4") (pintype "passive"))
      (node (ref "JP20") (pin "1") (pinfunction "1_1") (pintype "passive"))
      (node (ref "JP21") (pin "4") (pinfunction "4_4") (pintype "passive"))
      (node (ref "JP22") (pin "4") (pinfunction "4_4") (pintype "passive"))
      (node (ref "JP23") (pin "4") (pinfunction "4_4") (pintype "passive"))
      (node (ref "JP24") (pin "RXI") (pinfunction "2_RXI") (pintype "passive"))
      (node (ref "JP25") (pin "RXI") (pinfunction "2_RXI") (pintype "passive"))
      (node (ref "JP26") (pin "RXI") (pinfunction "2_RXI") (pintype "passive"))
      (node (ref "JP27") (pin "RXI") (pinfunction "2_RXI") (pintype "passive"))
      (node (ref "JP28") (pin "4") (pinfunction "4_4") (pintype "passive"))
      (node (ref "JP3") (pin "4") (pinfunction "4_4") (pintype "passive"))
      (node (ref "JP4") (pin "4") (pinfunction "4_4") (pintype "passive"))
      (node (ref "JP8") (pin "1") (pinfunction "1_1") (pintype "passive"))
      (node (ref "JP9") (pin "1") (pinfunction "1_1") (pintype "passive"))
      (node (ref "R1") (pin "1") (pinfunction "1_1") (pintype "passive"))
      (node (ref "R10") (pin "1") (pinfunction "1_1") (pintype "passive"))
      (node (ref "R11") (pin "1") (pinfunction "1_1") (pintype "passive"))
      (node (ref "R13") (pin "2") (pinfunction "2_2") (pintype "passive"))
      (node (ref "R2") (pin "1") (pinfunction "1_1") (pintype "passive"))
      (node (ref "R3") (pin "1") (pinfunction "1_1") (pintype "passive"))
      (node (ref "R4") (pin "1") (pinfunction "1_1") (pintype "passive"))
      (node (ref "R5") (pin "1") (pinfunction "1_1") (pintype "passive"))
      (node (ref "R6") (pin "1") (pinfunction "1_1") (pintype "passive"))
      (node (ref "R7") (pin "1") (pinfunction "1_1") (pintype "passive"))
      (node (ref "R8") (pin "1") (pinfunction "1_1") (pintype "passive"))
      (node (ref "R9") (pin "1") (pinfunction "1_1") (pintype "passive"))
    )
    (net (code "80") (name "VDD") (class "Default")
      (node (ref "IC1") (pin "6") (pinfunction "+VIN_6") (pintype "power_in"))
      (node (ref "POWER_DIST") (pin "2") (pinfunction "2_2") (pintype "passive"))
    )
    (net (code "81") (name "unconnected-(IC1-(T0)PD7-Pad65)") (class "Default")
      (node (ref "IC1") (pin "65") (pinfunction "(T0)PD7_65") (pintype "bidirectional"))
    )
    (net (code "82") (name "unconnected-(IC1-AREF-Pad46)") (class "Default")
      (node (ref "IC1") (pin "46") (pinfunction "AREF_46") (pintype "bidirectional"))
    )
    (net (code "83") (name "unconnected-(IC1-PG1(~{RD})-Pad67)") (class "Default")
      (node (ref "IC1") (pin "67") (pinfunction "PG1(~{RD})_67") (pintype "bidirectional"))
    )
    (net (code "84") (name "unconnected-(IC1-PL7-Pad69)") (class "Default")
      (node (ref "IC1") (pin "69") (pinfunction "PL7_69") (pintype "bidirectional"))
    )
  )
)
